# gate_driver_array.net
KiCad netlist of a schematic drawn in Altium Designer
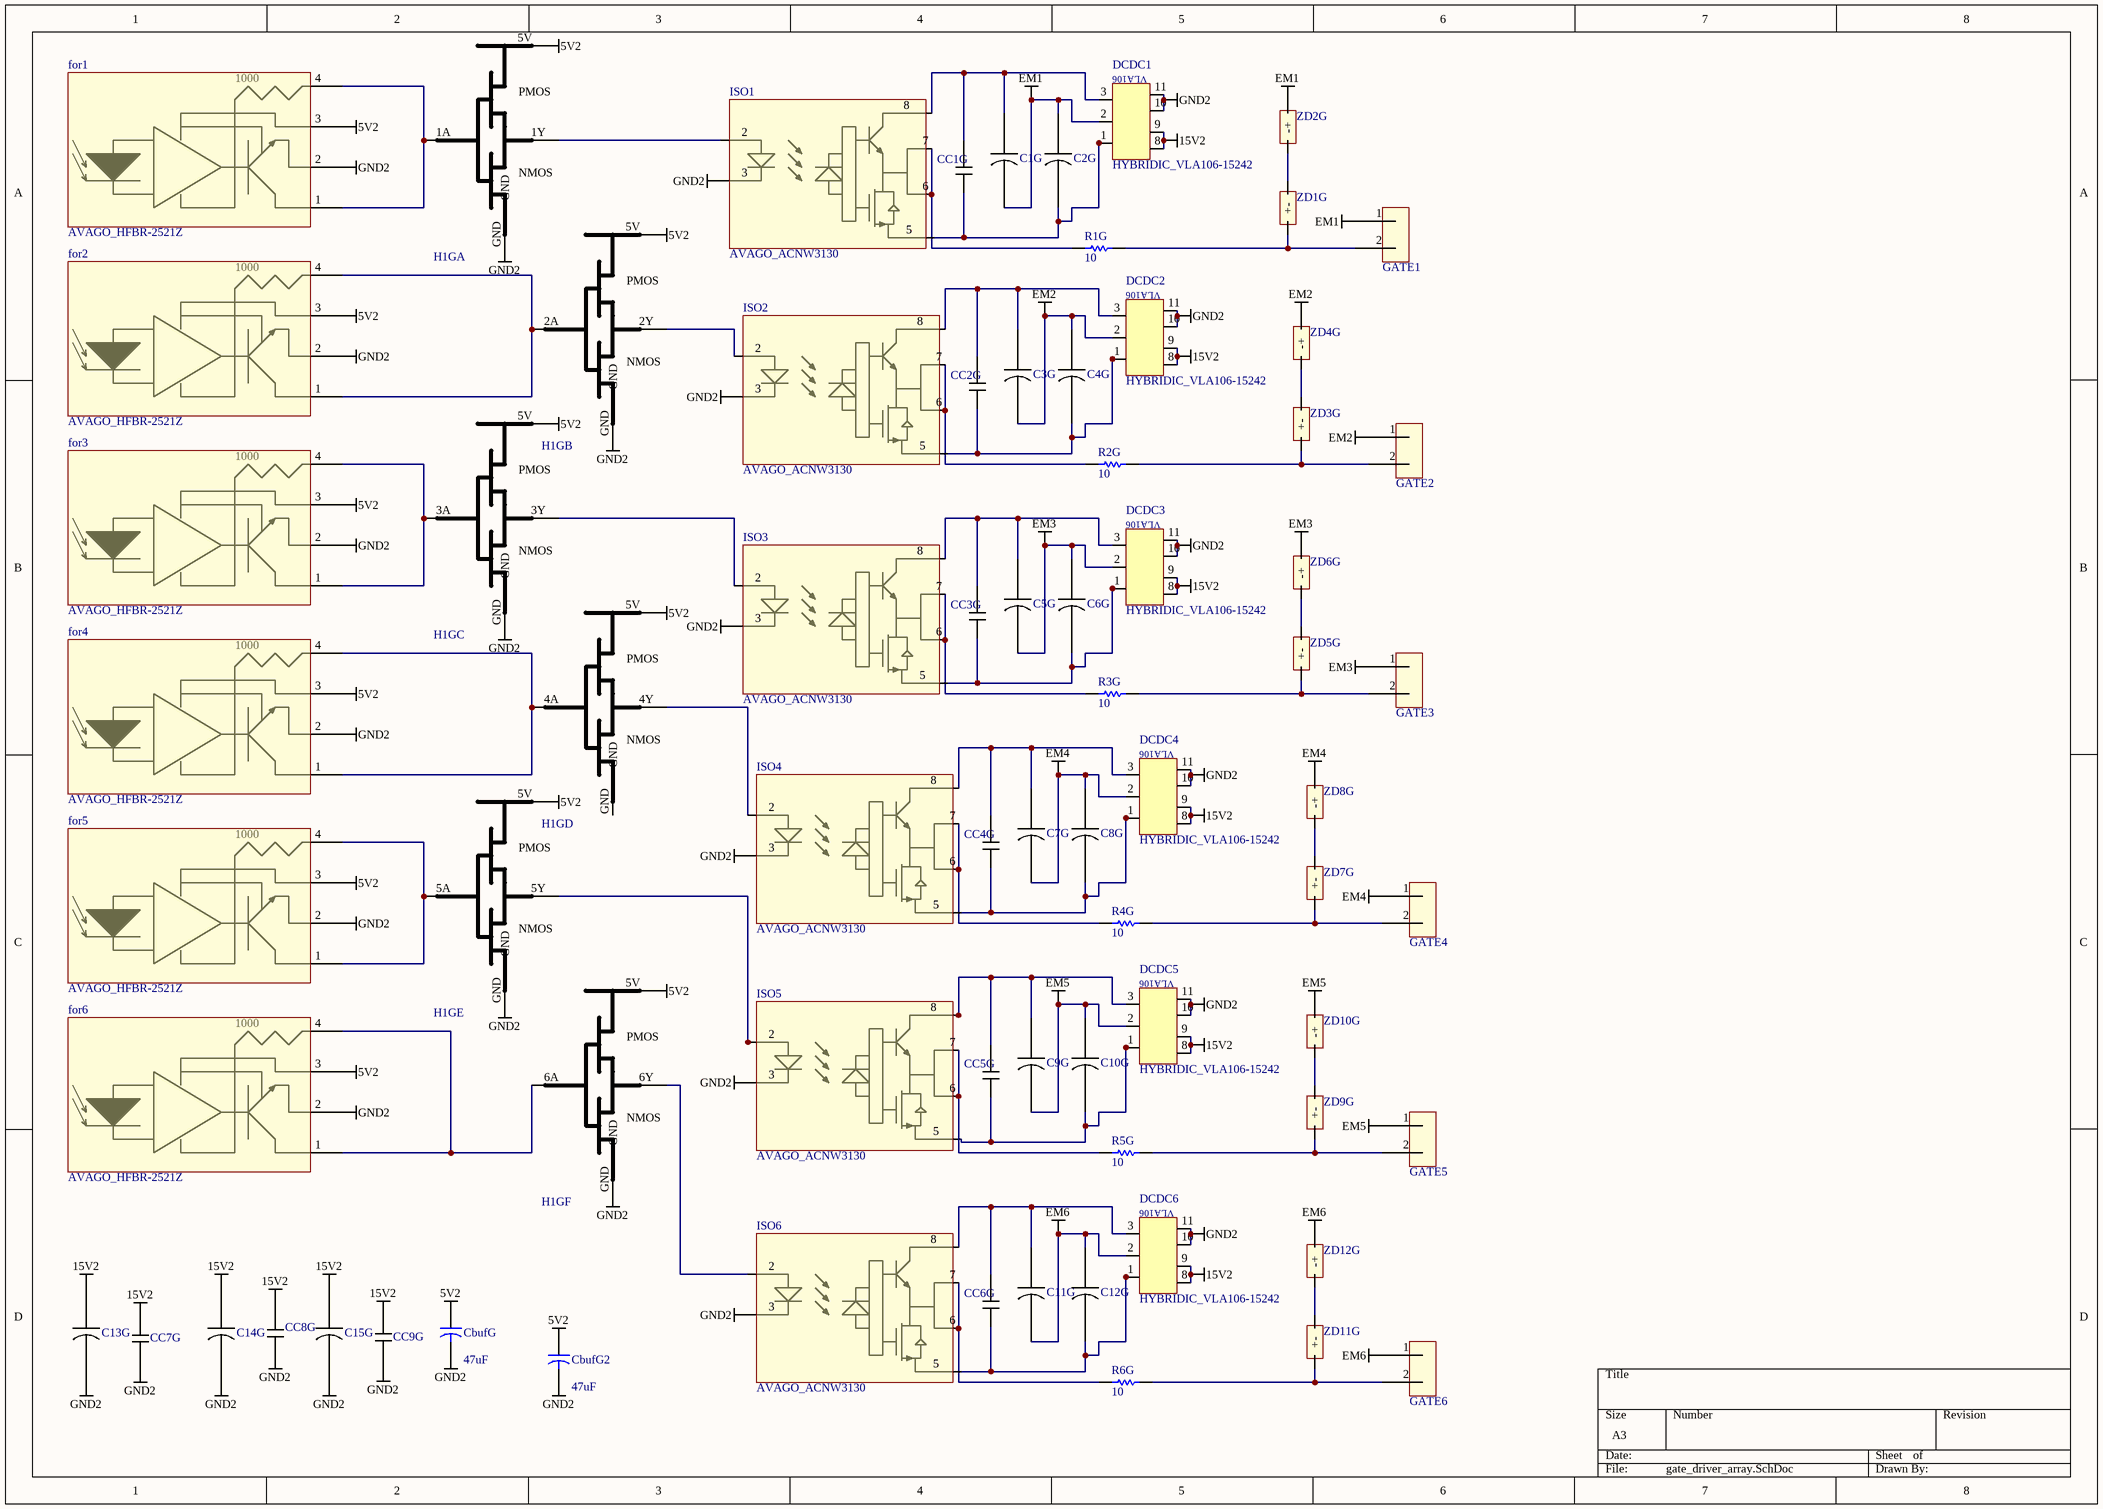
[diagram p0: gate_driver_array.SchDoc]

(export (version "E")
  (design (tool "Eeschema 10.0.6"))
  (components
    (comp (ref "C1G")
      (value "Cap_Pol_5")
      (footprint "Cap_Pol_5mm")
      (libsource (lib "smartChargerLibrary") (part "Cap_Pol_5"))
    )
    (comp (ref "C2G")
      (value "Cap_Pol_5")
      (footprint "Cap_Pol_5mm")
      (libsource (lib "smartChargerLibrary") (part "Cap_Pol_5"))
    )
    (comp (ref "C3G")
      (value "Cap_Pol_5")
      (footprint "Cap_Pol_5mm")
      (libsource (lib "smartChargerLibrary") (part "Cap_Pol_5"))
    )
    (comp (ref "C4G")
      (value "Cap_Pol_5")
      (footprint "Cap_Pol_5mm")
      (libsource (lib "smartChargerLibrary") (part "Cap_Pol_5"))
    )
    (comp (ref "C5G")
      (value "Cap_Pol_5")
      (footprint "Cap_Pol_5mm")
      (libsource (lib "smartChargerLibrary") (part "Cap_Pol_5"))
    )
    (comp (ref "C6G")
      (value "Cap_Pol_5")
      (footprint "Cap_Pol_5mm")
      (libsource (lib "smartChargerLibrary") (part "Cap_Pol_5"))
    )
    (comp (ref "C7G")
      (value "Cap_Pol_5")
      (footprint "Cap_Pol_5mm")
      (libsource (lib "smartChargerLibrary") (part "Cap_Pol_5"))
    )
    (comp (ref "C8G")
      (value "Cap_Pol_5")
      (footprint "Cap_Pol_5mm")
      (libsource (lib "smartChargerLibrary") (part "Cap_Pol_5"))
    )
    (comp (ref "C9G")
      (value "Cap_Pol_5")
      (footprint "Cap_Pol_5mm")
      (libsource (lib "smartChargerLibrary") (part "Cap_Pol_5"))
    )
    (comp (ref "C10G")
      (value "Cap_Pol_5")
      (footprint "Cap_Pol_5mm")
      (libsource (lib "smartChargerLibrary") (part "Cap_Pol_5"))
    )
    (comp (ref "C11G")
      (value "Cap_Pol_5")
      (footprint "Cap_Pol_5mm")
      (libsource (lib "smartChargerLibrary") (part "Cap_Pol_5"))
    )
    (comp (ref "C12G")
      (value "Cap_Pol_5")
      (footprint "Cap_Pol_5mm")
      (libsource (lib "smartChargerLibrary") (part "Cap_Pol_5"))
    )
    (comp (ref "C13G")
      (value "Cap_Pol_5")
      (footprint "Cap_Pol_5mm")
      (libsource (lib "smartChargerLibrary") (part "Cap_Pol_5"))
    )
    (comp (ref "C14G")
      (value "Cap_Pol_5")
      (footprint "Cap_Pol_5mm")
      (libsource (lib "smartChargerLibrary") (part "Cap_Pol_5"))
    )
    (comp (ref "C15G")
      (value "Cap_Pol_5")
      (footprint "Cap_Pol_5mm")
      (libsource (lib "smartChargerLibrary") (part "Cap_Pol_5"))
    )
    (comp (ref "CbufG")
      (value "47uF")
      (footprint "CAPR5-4X5")
      (description "Capacitor")
      (fields (field (name "Comment") "Cap2") (field (name "PUBLISHER") "Altium Limited"))
      (libsource (lib "Miscellaneous Devices") (part "Cap2"))
    )
    (comp (ref "CbufG2")
      (value "47uF")
      (footprint "CAPR5-4X5")
      (description "Capacitor")
      (fields (field (name "Comment") "Cap2") (field (name "PUBLISHER") "Altium Limited"))
      (libsource (lib "Miscellaneous Devices") (part "Cap2"))
    )
    (comp (ref "CC1G")
      (value "CAP_CERAM_5MM")
      (footprint "CAP_CERAM_5MM")
      (libsource (lib "smartChargerLibrary") (part "CAP_CERAM_5MM"))
    )
    (comp (ref "CC2G")
      (value "CAP_CERAM_5MM")
      (footprint "CAP_CERAM_5MM")
      (libsource (lib "smartChargerLibrary") (part "CAP_CERAM_5MM"))
    )
    (comp (ref "CC3G")
      (value "CAP_CERAM_5MM")
      (footprint "CAP_CERAM_5MM")
      (libsource (lib "smartChargerLibrary") (part "CAP_CERAM_5MM"))
    )
    (comp (ref "CC4G")
      (value "CAP_CERAM_5MM")
      (footprint "CAP_CERAM_5MM")
      (libsource (lib "smartChargerLibrary") (part "CAP_CERAM_5MM"))
    )
    (comp (ref "CC5G")
      (value "CAP_CERAM_5MM")
      (footprint "CAP_CERAM_5MM")
      (libsource (lib "smartChargerLibrary") (part "CAP_CERAM_5MM"))
    )
    (comp (ref "CC6G")
      (value "CAP_CERAM_5MM")
      (footprint "CAP_CERAM_5MM")
      (libsource (lib "smartChargerLibrary") (part "CAP_CERAM_5MM"))
    )
    (comp (ref "CC7G")
      (value "CAP_CERAM_5MM")
      (footprint "CAP_CERAM_5MM")
      (libsource (lib "smartChargerLibrary") (part "CAP_CERAM_5MM"))
    )
    (comp (ref "CC8G")
      (value "CAP_CERAM_5MM")
      (footprint "CAP_CERAM_5MM")
      (libsource (lib "smartChargerLibrary") (part "CAP_CERAM_5MM"))
    )
    (comp (ref "CC9G")
      (value "CAP_CERAM_5MM")
      (footprint "CAP_CERAM_5MM")
      (libsource (lib "smartChargerLibrary") (part "CAP_CERAM_5MM"))
    )
    (comp (ref "DCDC1")
      (value "HYBRIDIC_VLA106-15242")
      (footprint "HYBRIDIC_VLA106-15242")
      (description "Isolated DC/DC Converter")
      (libsource (lib "smartChargerLibrary") (part "HYBRIDIC_VLA106-15242"))
    )
    (comp (ref "DCDC2")
      (value "HYBRIDIC_VLA106-15242")
      (footprint "HYBRIDIC_VLA106-15242")
      (description "Isolated DC/DC Converter")
      (libsource (lib "smartChargerLibrary") (part "HYBRIDIC_VLA106-15242"))
    )
    (comp (ref "DCDC3")
      (value "HYBRIDIC_VLA106-15242")
      (footprint "HYBRIDIC_VLA106-15242")
      (description "Isolated DC/DC Converter")
      (libsource (lib "smartChargerLibrary") (part "HYBRIDIC_VLA106-15242"))
    )
    (comp (ref "DCDC4")
      (value "HYBRIDIC_VLA106-15242")
      (footprint "HYBRIDIC_VLA106-15242")
      (description "Isolated DC/DC Converter")
      (libsource (lib "smartChargerLibrary") (part "HYBRIDIC_VLA106-15242"))
    )
    (comp (ref "DCDC5")
      (value "HYBRIDIC_VLA106-15242")
      (footprint "HYBRIDIC_VLA106-15242")
      (description "Isolated DC/DC Converter")
      (libsource (lib "smartChargerLibrary") (part "HYBRIDIC_VLA106-15242"))
    )
    (comp (ref "DCDC6")
      (value "HYBRIDIC_VLA106-15242")
      (footprint "HYBRIDIC_VLA106-15242")
      (description "Isolated DC/DC Converter")
      (libsource (lib "smartChargerLibrary") (part "HYBRIDIC_VLA106-15242"))
    )
    (comp (ref "for1")
      (value "AVAGO_HFBR-2521Z")
      (footprint "AVAGO_HFBR-2521Z")
      (description "Optical Fiber Receiver")
      (libsource (lib "smartChargerLibrary") (part "AVAGO_HFBR-2521Z"))
    )
    (comp (ref "for2")
      (value "AVAGO_HFBR-2521Z")
      (footprint "AVAGO_HFBR-2521Z")
      (description "Optical Fiber Receiver")
      (libsource (lib "smartChargerLibrary") (part "AVAGO_HFBR-2521Z"))
    )
    (comp (ref "for3")
      (value "AVAGO_HFBR-2521Z")
      (footprint "AVAGO_HFBR-2521Z")
      (description "Optical Fiber Receiver")
      (libsource (lib "smartChargerLibrary") (part "AVAGO_HFBR-2521Z"))
    )
    (comp (ref "for4")
      (value "AVAGO_HFBR-2521Z")
      (footprint "AVAGO_HFBR-2521Z")
      (description "Optical Fiber Receiver")
      (libsource (lib "smartChargerLibrary") (part "AVAGO_HFBR-2521Z"))
    )
    (comp (ref "for5")
      (value "AVAGO_HFBR-2521Z")
      (footprint "AVAGO_HFBR-2521Z")
      (description "Optical Fiber Receiver")
      (libsource (lib "smartChargerLibrary") (part "AVAGO_HFBR-2521Z"))
    )
    (comp (ref "for6")
      (value "AVAGO_HFBR-2521Z")
      (footprint "AVAGO_HFBR-2521Z")
      (description "Optical Fiber Receiver")
      (libsource (lib "smartChargerLibrary") (part "AVAGO_HFBR-2521Z"))
    )
    (comp (ref "GATE1")
      (value "5MM_HOR_ENTRY")
      (footprint "5MM_HOR_ENTRY")
      (libsource (lib "smartChargerLibrary") (part "5MM_HOR_ENTRY"))
    )
    (comp (ref "GATE2")
      (value "5MM_HOR_ENTRY")
      (footprint "5MM_HOR_ENTRY")
      (libsource (lib "smartChargerLibrary") (part "5MM_HOR_ENTRY"))
    )
    (comp (ref "GATE3")
      (value "5MM_HOR_ENTRY")
      (footprint "5MM_HOR_ENTRY")
      (libsource (lib "smartChargerLibrary") (part "5MM_HOR_ENTRY"))
    )
    (comp (ref "GATE4")
      (value "5MM_HOR_ENTRY")
      (footprint "5MM_HOR_ENTRY")
      (libsource (lib "smartChargerLibrary") (part "5MM_HOR_ENTRY"))
    )
    (comp (ref "GATE5")
      (value "5MM_HOR_ENTRY")
      (footprint "5MM_HOR_ENTRY")
      (libsource (lib "smartChargerLibrary") (part "5MM_HOR_ENTRY"))
    )
    (comp (ref "GATE6")
      (value "5MM_HOR_ENTRY")
      (footprint "5MM_HOR_ENTRY")
      (libsource (lib "smartChargerLibrary") (part "5MM_HOR_ENTRY"))
    )
    (comp (ref "H1G")
      (value "TI_SN74HC04N")
      (footprint "SN74HC04N")
      (description "Hex Inverter 5V")
      (libsource (lib "smartChargerLibrary") (part "TI_SN74HC04N"))
    )
    (comp (ref "ISO1")
      (value "AVAGO_ACNW3130")
      (footprint "AVAGO_ACNW3130")
      (description "IGBT Gate Drive Optocoupler")
      (libsource (lib "smartChargerLibrary") (part "AVAGO_ACNW3130"))
    )
    (comp (ref "ISO2")
      (value "AVAGO_ACNW3130")
      (footprint "AVAGO_ACNW3130")
      (description "IGBT Gate Drive Optocoupler")
      (libsource (lib "smartChargerLibrary") (part "AVAGO_ACNW3130"))
    )
    (comp (ref "ISO3")
      (value "AVAGO_ACNW3130")
      (footprint "AVAGO_ACNW3130")
      (description "IGBT Gate Drive Optocoupler")
      (libsource (lib "smartChargerLibrary") (part "AVAGO_ACNW3130"))
    )
    (comp (ref "ISO4")
      (value "AVAGO_ACNW3130")
      (footprint "AVAGO_ACNW3130")
      (description "IGBT Gate Drive Optocoupler")
      (libsource (lib "smartChargerLibrary") (part "AVAGO_ACNW3130"))
    )
    (comp (ref "ISO5")
      (value "AVAGO_ACNW3130")
      (footprint "AVAGO_ACNW3130")
      (description "IGBT Gate Drive Optocoupler")
      (libsource (lib "smartChargerLibrary") (part "AVAGO_ACNW3130"))
    )
    (comp (ref "ISO6")
      (value "AVAGO_ACNW3130")
      (footprint "AVAGO_ACNW3130")
      (description "IGBT Gate Drive Optocoupler")
      (libsource (lib "smartChargerLibrary") (part "AVAGO_ACNW3130"))
    )
    (comp (ref "R1G")
      (value "10")
      (footprint "AXIAL-0.3")
      (description "Resistor")
      (fields (field (name "Comment") "Res1") (field (name "PUBLISHER") "Altium Limited"))
      (libsource (lib "Miscellaneous Devices") (part "Res1"))
    )
    (comp (ref "R2G")
      (value "10")
      (footprint "AXIAL-0.3")
      (description "Resistor")
      (fields (field (name "Comment") "Res1") (field (name "PUBLISHER") "Altium Limited"))
      (libsource (lib "Miscellaneous Devices") (part "Res1"))
    )
    (comp (ref "R3G")
      (value "10")
      (footprint "AXIAL-0.3")
      (description "Resistor")
      (fields (field (name "Comment") "Res1") (field (name "PUBLISHER") "Altium Limited"))
      (libsource (lib "Miscellaneous Devices") (part "Res1"))
    )
    (comp (ref "R4G")
      (value "10")
      (footprint "AXIAL-0.3")
      (description "Resistor")
      (fields (field (name "Comment") "Res1") (field (name "PUBLISHER") "Altium Limited"))
      (libsource (lib "Miscellaneous Devices") (part "Res1"))
    )
    (comp (ref "R5G")
      (value "10")
      (footprint "AXIAL-0.3")
      (description "Resistor")
      (fields (field (name "Comment") "Res1") (field (name "PUBLISHER") "Altium Limited"))
      (libsource (lib "Miscellaneous Devices") (part "Res1"))
    )
    (comp (ref "R6G")
      (value "10")
      (footprint "AXIAL-0.3")
      (description "Resistor")
      (fields (field (name "Comment") "Res1") (field (name "PUBLISHER") "Altium Limited"))
      (libsource (lib "Miscellaneous Devices") (part "Res1"))
    )
    (comp (ref "ZD1G") (value "ZENER_1W") (footprint "ZENER_1W") (libsource (lib "") (part "ZENER_1W_1")))
    (comp (ref "ZD2G")
      (value "ZENER_1W")
      (footprint "ZENER_1W")
      (libsource (lib "smartChargerLibrary") (part "ZENER_1W"))
    )
    (comp (ref "ZD3G") (value "ZENER_1W") (footprint "ZENER_1W") (libsource (lib "") (part "ZENER_1W_1")))
    (comp (ref "ZD4G")
      (value "ZENER_1W")
      (footprint "ZENER_1W")
      (libsource (lib "smartChargerLibrary") (part "ZENER_1W"))
    )
    (comp (ref "ZD5G") (value "ZENER_1W") (footprint "ZENER_1W") (libsource (lib "") (part "ZENER_1W_1")))
    (comp (ref "ZD6G")
      (value "ZENER_1W")
      (footprint "ZENER_1W")
      (libsource (lib "smartChargerLibrary") (part "ZENER_1W"))
    )
    (comp (ref "ZD7G") (value "ZENER_1W") (footprint "ZENER_1W") (libsource (lib "") (part "ZENER_1W_1")))
    (comp (ref "ZD8G")
      (value "ZENER_1W")
      (footprint "ZENER_1W")
      (libsource (lib "smartChargerLibrary") (part "ZENER_1W"))
    )
    (comp (ref "ZD9G") (value "ZENER_1W") (footprint "ZENER_1W") (libsource (lib "") (part "ZENER_1W_1")))
    (comp (ref "ZD10G")
      (value "ZENER_1W")
      (footprint "ZENER_1W")
      (libsource (lib "smartChargerLibrary") (part "ZENER_1W"))
    )
    (comp (ref "ZD11G") (value "ZENER_1W") (footprint "ZENER_1W") (libsource (lib "") (part "ZENER_1W_1")))
    (comp (ref "ZD12G")
      (value "ZENER_1W")
      (footprint "ZENER_1W")
      (libsource (lib "smartChargerLibrary") (part "ZENER_1W"))
    )
  )
  (nets
    (net (code "1") (name "5V2") (class "Default")
      (node (ref "CbufG") (pin "1") (pinfunction "1_1") (pintype "passive"))
      (node (ref "CbufG2") (pin "1") (pinfunction "1_1") (pintype "passive"))
      (node (ref "H1G") (pin "5V") (pinfunction "5V_5V") (pintype "power_in"))
      (node (ref "for1") (pin "3") (pinfunction "3_3") (pintype "power_in"))
      (node (ref "for2") (pin "3") (pinfunction "3_3") (pintype "power_in"))
      (node (ref "for3") (pin "3") (pinfunction "3_3") (pintype "power_in"))
      (node (ref "for4") (pin "3") (pinfunction "3_3") (pintype "power_in"))
      (node (ref "for5") (pin "3") (pinfunction "3_3") (pintype "power_in"))
      (node (ref "for6") (pin "3") (pinfunction "3_3") (pintype "power_in"))
    )
    (net (code "2") (name "15V2") (class "Default")
      (node (ref "C13G") (pin "1") (pinfunction "1_1") (pintype "passive"))
      (node (ref "C14G") (pin "1") (pinfunction "1_1") (pintype "passive"))
      (node (ref "C15G") (pin "1") (pinfunction "1_1") (pintype "passive"))
      (node (ref "CC7G") (pin "2") (pinfunction "2_2") (pintype "passive"))
      (node (ref "CC8G") (pin "1") (pinfunction "1_1") (pintype "passive"))
      (node (ref "CC9G") (pin "2") (pinfunction "2_2") (pintype "passive"))
      (node (ref "DCDC1") (pin "8") (pinfunction "8_8") (pintype "passive"))
      (node (ref "DCDC1") (pin "9") (pinfunction "9_9") (pintype "passive"))
      (node (ref "DCDC2") (pin "8") (pinfunction "8_8") (pintype "passive"))
      (node (ref "DCDC2") (pin "9") (pinfunction "9_9") (pintype "passive"))
      (node (ref "DCDC3") (pin "8") (pinfunction "8_8") (pintype "passive"))
      (node (ref "DCDC3") (pin "9") (pinfunction "9_9") (pintype "passive"))
      (node (ref "DCDC4") (pin "8") (pinfunction "8_8") (pintype "passive"))
      (node (ref "DCDC4") (pin "9") (pinfunction "9_9") (pintype "passive"))
      (node (ref "DCDC5") (pin "8") (pinfunction "8_8") (pintype "passive"))
      (node (ref "DCDC5") (pin "9") (pinfunction "9_9") (pintype "passive"))
      (node (ref "DCDC6") (pin "8") (pinfunction "8_8") (pintype "passive"))
      (node (ref "DCDC6") (pin "9") (pinfunction "9_9") (pintype "passive"))
    )
    (net (code "3") (name "EM1") (class "Default")
      (node (ref "C1G") (pin "2") (pinfunction "2_2") (pintype "passive"))
      (node (ref "C2G") (pin "1") (pinfunction "1_1") (pintype "passive"))
      (node (ref "DCDC1") (pin "2") (pinfunction "2_2") (pintype "passive"))
      (node (ref "GATE1") (pin "1") (pinfunction "1_1") (pintype "passive"))
      (node (ref "ZD2G") (pin "1") (pinfunction "+_1") (pintype "passive"))
    )
    (net (code "4") (name "EM2") (class "Default")
      (node (ref "C3G") (pin "2") (pinfunction "2_2") (pintype "passive"))
      (node (ref "C4G") (pin "1") (pinfunction "1_1") (pintype "passive"))
      (node (ref "DCDC2") (pin "2") (pinfunction "2_2") (pintype "passive"))
      (node (ref "GATE2") (pin "1") (pinfunction "1_1") (pintype "passive"))
      (node (ref "ZD4G") (pin "1") (pinfunction "+_1") (pintype "passive"))
    )
    (net (code "5") (name "EM3") (class "Default")
      (node (ref "C5G") (pin "2") (pinfunction "2_2") (pintype "passive"))
      (node (ref "C6G") (pin "1") (pinfunction "1_1") (pintype "passive"))
      (node (ref "DCDC3") (pin "2") (pinfunction "2_2") (pintype "passive"))
      (node (ref "GATE3") (pin "1") (pinfunction "1_1") (pintype "passive"))
      (node (ref "ZD6G") (pin "1") (pinfunction "+_1") (pintype "passive"))
    )
    (net (code "6") (name "EM4") (class "Default")
      (node (ref "C7G") (pin "2") (pinfunction "2_2") (pintype "passive"))
      (node (ref "C8G") (pin "1") (pinfunction "1_1") (pintype "passive"))
      (node (ref "DCDC4") (pin "2") (pinfunction "2_2") (pintype "passive"))
      (node (ref "GATE4") (pin "1") (pinfunction "1_1") (pintype "passive"))
      (node (ref "ZD8G") (pin "1") (pinfunction "+_1") (pintype "passive"))
    )
    (net (code "7") (name "EM5") (class "Default")
      (node (ref "C10G") (pin "1") (pinfunction "1_1") (pintype "passive"))
      (node (ref "C9G") (pin "2") (pinfunction "2_2") (pintype "passive"))
      (node (ref "DCDC5") (pin "2") (pinfunction "2_2") (pintype "passive"))
      (node (ref "GATE5") (pin "1") (pinfunction "1_1") (pintype "passive"))
      (node (ref "ZD10G") (pin "1") (pinfunction "+_1") (pintype "passive"))
    )
    (net (code "8") (name "EM6") (class "Default")
      (node (ref "C11G") (pin "2") (pinfunction "2_2") (pintype "passive"))
      (node (ref "C12G") (pin "1") (pinfunction "1_1") (pintype "passive"))
      (node (ref "DCDC6") (pin "2") (pinfunction "2_2") (pintype "passive"))
      (node (ref "GATE6") (pin "1") (pinfunction "1_1") (pintype "passive"))
      (node (ref "ZD12G") (pin "1") (pinfunction "+_1") (pintype "passive"))
    )
    (net (code "9") (name "GND2") (class "Default")
      (node (ref "C13G") (pin "2") (pinfunction "2_2") (pintype "passive"))
      (node (ref "C14G") (pin "2") (pinfunction "2_2") (pintype "passive"))
      (node (ref "C15G") (pin "2") (pinfunction "2_2") (pintype "passive"))
      (node (ref "CC7G") (pin "1") (pinfunction "1_1") (pintype "passive"))
      (node (ref "CC8G") (pin "2") (pinfunction "2_2") (pintype "passive"))
      (node (ref "CC9G") (pin "1") (pinfunction "1_1") (pintype "passive"))
      (node (ref "CbufG") (pin "2") (pinfunction "2_2") (pintype "passive"))
      (node (ref "CbufG2") (pin "2") (pinfunction "2_2") (pintype "passive"))
      (node (ref "DCDC1") (pin "10") (pinfunction "10_10") (pintype "passive"))
      (node (ref "DCDC1") (pin "11") (pinfunction "11_11") (pintype "passive"))
      (node (ref "DCDC2") (pin "10") (pinfunction "10_10") (pintype "passive"))
      (node (ref "DCDC2") (pin "11") (pinfunction "11_11") (pintype "passive"))
      (node (ref "DCDC3") (pin "10") (pinfunction "10_10") (pintype "passive"))
      (node (ref "DCDC3") (pin "11") (pinfunction "11_11") (pintype "passive"))
      (node (ref "DCDC4") (pin "10") (pinfunction "10_10") (pintype "passive"))
      (node (ref "DCDC4") (pin "11") (pinfunction "11_11") (pintype "passive"))
      (node (ref "DCDC5") (pin "10") (pinfunction "10_10") (pintype "passive"))
      (node (ref "DCDC5") (pin "11") (pinfunction "11_11") (pintype "passive"))
      (node (ref "DCDC6") (pin "10") (pinfunction "10_10") (pintype "passive"))
      (node (ref "DCDC6") (pin "11") (pinfunction "11_11") (pintype "passive"))
      (node (ref "H1G") (pin "GND") (pinfunction "GND_GND") (pintype "power_in"))
      (node (ref "ISO1") (pin "3") (pinfunction "3_3") (pintype "passive"))
      (node (ref "ISO2") (pin "3") (pinfunction "3_3") (pintype "passive"))
      (node (ref "ISO3") (pin "3") (pinfunction "3_3") (pintype "passive"))
      (node (ref "ISO4") (pin "3") (pinfunction "3_3") (pintype "passive"))
      (node (ref "ISO5") (pin "3") (pinfunction "3_3") (pintype "passive"))
      (node (ref "ISO6") (pin "3") (pinfunction "3_3") (pintype "passive"))
      (node (ref "for1") (pin "2") (pinfunction "2_2") (pintype "power_in"))
      (node (ref "for2") (pin "2") (pinfunction "2_2") (pintype "power_in"))
      (node (ref "for3") (pin "2") (pinfunction "2_2") (pintype "power_in"))
      (node (ref "for4") (pin "2") (pinfunction "2_2") (pintype "power_in"))
      (node (ref "for5") (pin "2") (pinfunction "2_2") (pintype "power_in"))
      (node (ref "for6") (pin "2") (pinfunction "2_2") (pintype "power_in"))
    )
    (net (code "10") (name "Net-(C1G-Pad1)") (class "Default")
      (node (ref "C1G") (pin "1") (pinfunction "1_1") (pintype "passive"))
      (node (ref "CC1G") (pin "1") (pinfunction "1_1") (pintype "passive"))
      (node (ref "DCDC1") (pin "3") (pinfunction "3_3") (pintype "passive"))
      (node (ref "ISO1") (pin "8") (pinfunction "8_8") (pintype "passive"))
    )
    (net (code "11") (name "Net-(C2G-Pad2)") (class "Default")
      (node (ref "C2G") (pin "2") (pinfunction "2_2") (pintype "passive"))
      (node (ref "CC1G") (pin "2") (pinfunction "2_2") (pintype "passive"))
      (node (ref "DCDC1") (pin "1") (pinfunction "1_1") (pintype "passive"))
      (node (ref "ISO1") (pin "5") (pinfunction "5_5") (pintype "passive"))
    )
    (net (code "12") (name "Net-(C3G-Pad1)") (class "Default")
      (node (ref "C3G") (pin "1") (pinfunction "1_1") (pintype "passive"))
      (node (ref "CC2G") (pin "1") (pinfunction "1_1") (pintype "passive"))
      (node (ref "DCDC2") (pin "3") (pinfunction "3_3") (pintype "passive"))
      (node (ref "ISO2") (pin "8") (pinfunction "8_8") (pintype "passive"))
    )
    (net (code "13") (name "Net-(C4G-Pad2)") (class "Default")
      (node (ref "C4G") (pin "2") (pinfunction "2_2") (pintype "passive"))
      (node (ref "CC2G") (pin "2") (pinfunction "2_2") (pintype "passive"))
      (node (ref "DCDC2") (pin "1") (pinfunction "1_1") (pintype "passive"))
      (node (ref "ISO2") (pin "5") (pinfunction "5_5") (pintype "passive"))
    )
    (net (code "14") (name "Net-(C5G-Pad1)") (class "Default")
      (node (ref "C5G") (pin "1") (pinfunction "1_1") (pintype "passive"))
      (node (ref "CC3G") (pin "1") (pinfunction "1_1") (pintype "passive"))
      (node (ref "DCDC3") (pin "3") (pinfunction "3_3") (pintype "passive"))
      (node (ref "ISO3") (pin "8") (pinfunction "8_8") (pintype "passive"))
    )
    (net (code "15") (name "Net-(C6G-Pad2)") (class "Default")
      (node (ref "C6G") (pin "2") (pinfunction "2_2") (pintype "passive"))
      (node (ref "CC3G") (pin "2") (pinfunction "2_2") (pintype "passive"))
      (node (ref "DCDC3") (pin "1") (pinfunction "1_1") (pintype "passive"))
      (node (ref "ISO3") (pin "5") (pinfunction "5_5") (pintype "passive"))
    )
    (net (code "16") (name "Net-(C7G-Pad1)") (class "Default")
      (node (ref "C7G") (pin "1") (pinfunction "1_1") (pintype "passive"))
      (node (ref "CC4G") (pin "1") (pinfunction "1_1") (pintype "passive"))
      (node (ref "DCDC4") (pin "3") (pinfunction "3_3") (pintype "passive"))
      (node (ref "ISO4") (pin "8") (pinfunction "8_8") (pintype "passive"))
    )
    (net (code "17") (name "Net-(C8G-Pad2)") (class "Default")
      (node (ref "C8G") (pin "2") (pinfunction "2_2") (pintype "passive"))
      (node (ref "CC4G") (pin "2") (pinfunction "2_2") (pintype "passive"))
      (node (ref "DCDC4") (pin "1") (pinfunction "1_1") (pintype "passive"))
      (node (ref "ISO4") (pin "5") (pinfunction "5_5") (pintype "passive"))
    )
    (net (code "18") (name "Net-(C9G-Pad1)") (class "Default")
      (node (ref "C9G") (pin "1") (pinfunction "1_1") (pintype "passive"))
      (node (ref "CC5G") (pin "1") (pinfunction "1_1") (pintype "passive"))
      (node (ref "DCDC5") (pin "3") (pinfunction "3_3") (pintype "passive"))
      (node (ref "ISO5") (pin "8") (pinfunction "8_8") (pintype "passive"))
    )
    (net (code "19") (name "Net-(C10G-Pad2)") (class "Default")
      (node (ref "C10G") (pin "2") (pinfunction "2_2") (pintype "passive"))
      (node (ref "CC5G") (pin "2") (pinfunction "2_2") (pintype "passive"))
      (node (ref "DCDC5") (pin "1") (pinfunction "1_1") (pintype "passive"))
      (node (ref "ISO5") (pin "5") (pinfunction "5_5") (pintype "passive"))
    )
    (net (code "20") (name "Net-(C11G-Pad1)") (class "Default")
      (node (ref "C11G") (pin "1") (pinfunction "1_1") (pintype "passive"))
      (node (ref "CC6G") (pin "1") (pinfunction "1_1") (pintype "passive"))
      (node (ref "DCDC6") (pin "3") (pinfunction "3_3") (pintype "passive"))
      (node (ref "ISO6") (pin "8") (pinfunction "8_8") (pintype "passive"))
    )
    (net (code "21") (name "Net-(C12G-Pad2)") (class "Default")
      (node (ref "C12G") (pin "2") (pinfunction "2_2") (pintype "passive"))
      (node (ref "CC6G") (pin "2") (pinfunction "2_2") (pintype "passive"))
      (node (ref "DCDC6") (pin "1") (pinfunction "1_1") (pintype "passive"))
      (node (ref "ISO6") (pin "5") (pinfunction "5_5") (pintype "passive"))
    )
    (net (code "22") (name "Net-(H1G-Pad1A)") (class "Default")
      (node (ref "H1G") (pin "1A") (pinfunction "1A_1A") (pintype "passive"))
      (node (ref "for1") (pin "1") (pinfunction "1_1") (pintype "passive"))
      (node (ref "for1") (pin "4") (pinfunction "4_4") (pintype "passive"))
    )
    (net (code "23") (name "Net-(H1G-Pad1Y)") (class "Default")
      (node (ref "H1G") (pin "1Y") (pinfunction "1Y_1Y") (pintype "passive"))
      (node (ref "ISO1") (pin "2") (pinfunction "2_2") (pintype "passive"))
    )
    (net (code "24") (name "Net-(H1G-Pad2A)") (class "Default")
      (node (ref "H1G") (pin "2A") (pinfunction "2A_2A") (pintype "passive"))
      (node (ref "for2") (pin "1") (pinfunction "1_1") (pintype "passive"))
      (node (ref "for2") (pin "4") (pinfunction "4_4") (pintype "passive"))
    )
    (net (code "25") (name "Net-(H1G-Pad2Y)") (class "Default")
      (node (ref "H1G") (pin "2Y") (pinfunction "2Y_2Y") (pintype "passive"))
      (node (ref "ISO2") (pin "2") (pinfunction "2_2") (pintype "passive"))
    )
    (net (code "26") (name "Net-(H1G-Pad3A)") (class "Default")
      (node (ref "H1G") (pin "3A") (pinfunction "3A_3A") (pintype "passive"))
      (node (ref "for3") (pin "1") (pinfunction "1_1") (pintype "passive"))
      (node (ref "for3") (pin "4") (pinfunction "4_4") (pintype "passive"))
    )
    (net (code "27") (name "Net-(H1G-Pad3Y)") (class "Default")
      (node (ref "H1G") (pin "3Y") (pinfunction "3Y_3Y") (pintype "passive"))
      (node (ref "ISO3") (pin "2") (pinfunction "2_2") (pintype "passive"))
    )
    (net (code "28") (name "Net-(H1G-Pad4A)") (class "Default")
      (node (ref "H1G") (pin "4A") (pinfunction "4A_4A") (pintype "passive"))
      (node (ref "for4") (pin "1") (pinfunction "1_1") (pintype "passive"))
      (node (ref "for4") (pin "4") (pinfunction "4_4") (pintype "passive"))
    )
    (net (code "29") (name "Net-(H1G-Pad4Y)") (class "Default")
      (node (ref "H1G") (pin "4Y") (pinfunction "4Y_4Y") (pintype "passive"))
      (node (ref "ISO4") (pin "2") (pinfunction "2_2") (pintype "passive"))
    )
    (net (code "30") (name "Net-(H1G-Pad5A)") (class "Default")
      (node (ref "H1G") (pin "5A") (pinfunction "5A_5A") (pintype "passive"))
      (node (ref "for5") (pin "1") (pinfunction "1_1") (pintype "passive"))
      (node (ref "for5") (pin "4") (pinfunction "4_4") (pintype "passive"))
    )
    (net (code "31") (name "Net-(H1G-Pad5Y)") (class "Default")
      (node (ref "H1G") (pin "5Y") (pinfunction "5Y_5Y") (pintype "passive"))
      (node (ref "ISO5") (pin "2") (pinfunction "2_2") (pintype "passive"))
    )
    (net (code "32") (name "Net-(H1G-Pad6A)") (class "Default")
      (node (ref "H1G") (pin "6A") (pinfunction "6A_6A") (pintype "passive"))
      (node (ref "for6") (pin "1") (pinfunction "1_1") (pintype "passive"))
      (node (ref "for6") (pin "4") (pinfunction "4_4") (pintype "passive"))
    )
    (net (code "33") (name "Net-(H1G-Pad6Y)") (class "Default")
      (node (ref "H1G") (pin "6Y") (pinfunction "6Y_6Y") (pintype "passive"))
      (node (ref "ISO6") (pin "2") (pinfunction "2_2") (pintype "passive"))
    )
    (net (code "34") (name "Net-(ISO1-Pad6)") (class "Default")
      (node (ref "ISO1") (pin "6") (pinfunction "6_6") (pintype "passive"))
      (node (ref "ISO1") (pin "7") (pinfunction "7_7") (pintype "passive"))
      (node (ref "R1G") (pin "1") (pinfunction "1_1") (pintype "passive"))
    )
    (net (code "35") (name "Net-(ISO2-Pad6)") (class "Default")
      (node (ref "ISO2") (pin "6") (pinfunction "6_6") (pintype "passive"))
      (node (ref "ISO2") (pin "7") (pinfunction "7_7") (pintype "passive"))
      (node (ref "R2G") (pin "1") (pinfunction "1_1") (pintype "passive"))
    )
    (net (code "36") (name "Net-(ISO3-Pad6)") (class "Default")
      (node (ref "ISO3") (pin "6") (pinfunction "6_6") (pintype "passive"))
      (node (ref "ISO3") (pin "7") (pinfunction "7_7") (pintype "passive"))
      (node (ref "R3G") (pin "1") (pinfunction "1_1") (pintype "passive"))
    )
    (net (code "37") (name "Net-(ISO4-Pad6)") (class "Default")
      (node (ref "ISO4") (pin "6") (pinfunction "6_6") (pintype "passive"))
      (node (ref "ISO4") (pin "7") (pinfunction "7_7") (pintype "passive"))
      (node (ref "R4G") (pin "1") (pinfunction "1_1") (pintype "passive"))
    )
    (net (code "38") (name "Net-(ISO5-Pad6)") (class "Default")
      (node (ref "ISO5") (pin "6") (pinfunction "6_6") (pintype "passive"))
      (node (ref "ISO5") (pin "7") (pinfunction "7_7") (pintype "passive"))
      (node (ref "R5G") (pin "1") (pinfunction "1_1") (pintype "passive"))
    )
    (net (code "39") (name "Net-(ISO6-Pad6)") (class "Default")
      (node (ref "ISO6") (pin "6") (pinfunction "6_6") (pintype "passive"))
      (node (ref "ISO6") (pin "7") (pinfunction "7_7") (pintype "passive"))
      (node (ref "R6G") (pin "1") (pinfunction "1_1") (pintype "passive"))
    )
    (net (code "40") (name "Net-(ZD1G-+)") (class "Default")
      (node (ref "GATE1") (pin "2") (pinfunction "2_2") (pintype "passive"))
      (node (ref "R1G") (pin "2") (pinfunction "2_2") (pintype "passive"))
      (node (ref "ZD1G") (pin "1") (pinfunction "+_1") (pintype "passive"))
    )
    (net (code "41") (name "Net-(ZD1G--)") (class "Default")
      (node (ref "ZD1G") (pin "2") (pinfunction "-_2") (pintype "passive"))
      (node (ref "ZD2G") (pin "2") (pinfunction "-_2") (pintype "passive"))
    )
    (net (code "42") (name "Net-(ZD3G-+)") (class "Default")
      (node (ref "GATE2") (pin "2") (pinfunction "2_2") (pintype "passive"))
      (node (ref "R2G") (pin "2") (pinfunction "2_2") (pintype "passive"))
      (node (ref "ZD3G") (pin "1") (pinfunction "+_1") (pintype "passive"))
    )
    (net (code "43") (name "Net-(ZD3G--)") (class "Default")
      (node (ref "ZD3G") (pin "2") (pinfunction "-_2") (pintype "passive"))
      (node (ref "ZD4G") (pin "2") (pinfunction "-_2") (pintype "passive"))
    )
    (net (code "44") (name "Net-(ZD5G-+)") (class "Default")
      (node (ref "GATE3") (pin "2") (pinfunction "2_2") (pintype "passive"))
      (node (ref "R3G") (pin "2") (pinfunction "2_2") (pintype "passive"))
      (node (ref "ZD5G") (pin "1") (pinfunction "+_1") (pintype "passive"))
    )
    (net (code "45") (name "Net-(ZD5G--)") (class "Default")
      (node (ref "ZD5G") (pin "2") (pinfunction "-_2") (pintype "passive"))
      (node (ref "ZD6G") (pin "2") (pinfunction "-_2") (pintype "passive"))
    )
    (net (code "46") (name "Net-(ZD7G-+)") (class "Default")
      (node (ref "GATE4") (pin "2") (pinfunction "2_2") (pintype "passive"))
      (node (ref "R4G") (pin "2") (pinfunction "2_2") (pintype "passive"))
      (node (ref "ZD7G") (pin "1") (pinfunction "+_1") (pintype "passive"))
    )
    (net (code "47") (name "Net-(ZD7G--)") (class "Default")
      (node (ref "ZD7G") (pin "2") (pinfunction "-_2") (pintype "passive"))
      (node (ref "ZD8G") (pin "2") (pinfunction "-_2") (pintype "passive"))
    )
    (net (code "48") (name "Net-(ZD9G-+)") (class "Default")
      (node (ref "GATE5") (pin "2") (pinfunction "2_2") (pintype "passive"))
      (node (ref "R5G") (pin "2") (pinfunction "2_2") (pintype "passive"))
      (node (ref "ZD9G") (pin "1") (pinfunction "+_1") (pintype "passive"))
    )
    (net (code "49") (name "Net-(ZD10G--)") (class "Default")
      (node (ref "ZD10G") (pin "2") (pinfunction "-_2") (pintype "passive"))
      (node (ref "ZD9G") (pin "2") (pinfunction "-_2") (pintype "passive"))
    )
    (net (code "50") (name "Net-(ZD11G-+)") (class "Default")
      (node (ref "GATE6") (pin "2") (pinfunction "2_2") (pintype "passive"))
      (node (ref "R6G") (pin "2") (pinfunction "2_2") (pintype "passive"))
      (node (ref "ZD11G") (pin "1") (pinfunction "+_1") (pintype "passive"))
    )
    (net (code "51") (name "Net-(ZD11G--)") (class "Default")
      (node (ref "ZD11G") (pin "2") (pinfunction "-_2") (pintype "passive"))
      (node (ref "ZD12G") (pin "2") (pinfunction "-_2") (pintype "passive"))
    )
    (net (code "52") (name "unconnected-(H1G-PadGND)") (class "Default")
      (node (ref "H1G") (pin "GND") (pinfunction "GND_GND") (pintype "power_in"))
    )
  )
)
